# CAN_Shield_Board5.net
KiCad netlist of a schematic drawn in EAGLE
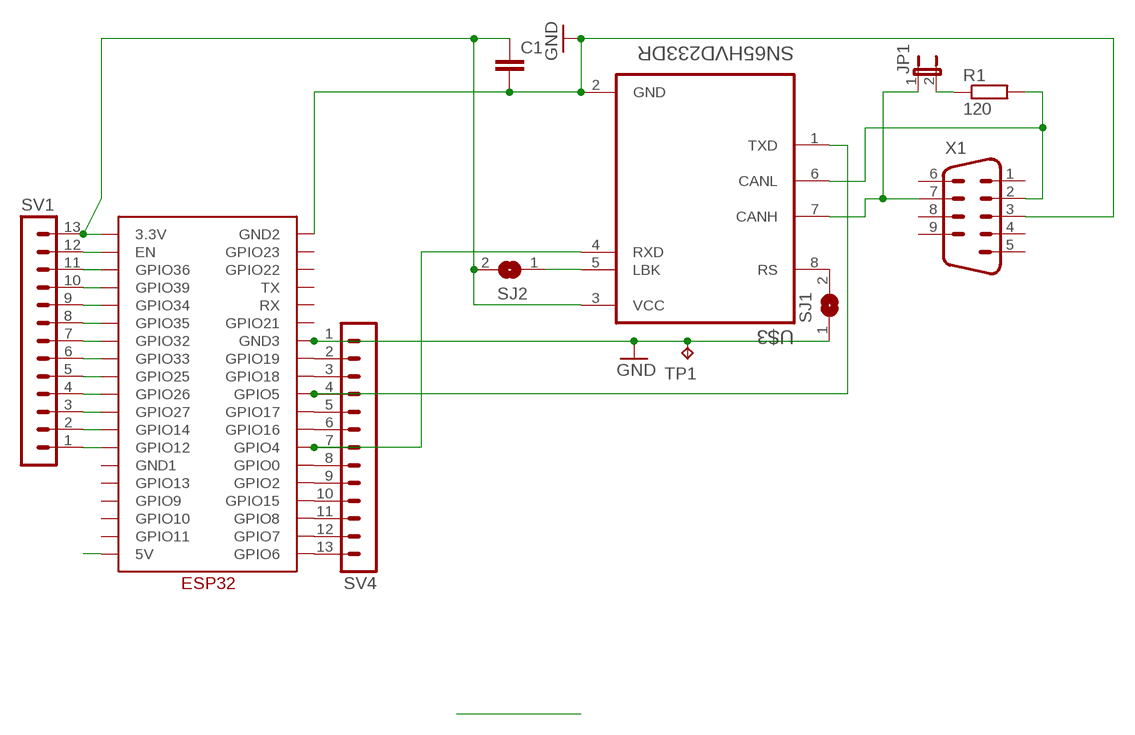
[diagram p0: schematic, sheet 1]

(export (version "E")
  (design (tool "Eeschema 10.0.6"))
  (components
    (comp (ref "C1")
      (value "C-EUC0805")
      (footprint "eagle-import:C0805")
      (libsource (lib "eagle-import") (part "C-EUC0805"))
    )
    (comp (ref "JP1")
      (value "JP1E")
      (footprint "eagle-import:JP1")
      (libsource (lib "eagle-import") (part "JP1E"))
    )
    (comp (ref "R1")
      (value "120")
      (footprint "eagle-import:R0805")
      (libsource (lib "eagle-import") (part "R-EU_R0805"))
    )
    (comp (ref "SJ1") (value "SJ") (footprint "eagle-import:SJ") (libsource (lib "eagle-import") (part "SJ")))
    (comp (ref "SJ2") (value "SJ") (footprint "eagle-import:SJ") (libsource (lib "eagle-import") (part "SJ")))
    (comp (ref "SV1")
      (value "MA13-1")
      (footprint "eagle-import:MA13-1")
      (libsource (lib "eagle-import") (part "MA13-1"))
    )
    (comp (ref "SV4")
      (value "MA13-1")
      (footprint "eagle-import:MA13-1")
      (libsource (lib "eagle-import") (part "MA13-1"))
    )
    (comp (ref "TP1")
      (value "TPPAD1-13Y")
      (footprint "eagle-import:P1-13Y")
      (libsource (lib "eagle-import") (part "TPPAD1-13Y"))
    )
    (comp (ref "U$1")
      (value "ESP32")
      (footprint "eagle-import:ESP32")
      (libsource (lib "eagle-import") (part "ESP32"))
    )
    (comp (ref "U$3")
      (value "SN65HVD233DR")
      (footprint "eagle-import:SOIC127P599X175-8N")
      (fields (field (name "MF") "Texas Instruments"))
      (libsource (lib "eagle-import") (part "SN65HVD233DR"))
    )
    (comp (ref "X1")
      (value "M09HP")
      (footprint "eagle-import:M09HP")
      (libsource (lib "eagle-import") (part "M09HP"))
    )
  )
  (nets
    (net (code "1") (name "GND") (class "Default")
      (node (ref "C1") (pin "2") (pinfunction "2_2") (pintype "passive"))
      (node (ref "SJ1") (pin "1") (pinfunction "1_1") (pintype "passive"))
      (node (ref "SV4") (pin "1") (pinfunction "1_1") (pintype "passive"))
      (node (ref "TP1") (pin "TP") (pinfunction "TP_TP") (pintype "input"))
      (node (ref "U$1") (pin "GND2") (pinfunction "GND2_GND2") (pintype "bidirectional"))
      (node (ref "U$1") (pin "GND3") (pinfunction "GND3_GND3") (pintype "bidirectional"))
      (node (ref "U$3") (pin "2") (pinfunction "GND_2") (pintype "power_in"))
      (node (ref "X1") (pin "3") (pinfunction "3_3") (pintype "passive"))
    )
    (net (code "2") (name "Net-(JP1-Pad2)") (class "Default")
      (node (ref "JP1") (pin "2") (pinfunction "2_2") (pintype "passive"))
      (node (ref "R1") (pin "1") (pinfunction "1_1") (pintype "passive"))
    )
    (net (code "3") (name "Net-(SV1-Pad1)") (class "Default")
      (node (ref "SV1") (pin "1") (pinfunction "1_1") (pintype "passive"))
      (node (ref "U$1") (pin "GPIO12") (pinfunction "GPIO12_GPIO12") (pintype "bidirectional"))
    )
    (net (code "4") (name "Net-(SV1-Pad2)") (class "Default")
      (node (ref "SV1") (pin "2") (pinfunction "2_2") (pintype "passive"))
      (node (ref "U$1") (pin "GPIO14") (pinfunction "GPIO14_GPIO14") (pintype "bidirectional"))
    )
    (net (code "5") (name "Net-(SV1-Pad3)") (class "Default")
      (node (ref "SV1") (pin "3") (pinfunction "3_3") (pintype "passive"))
      (node (ref "U$1") (pin "GPIO27") (pinfunction "GPIO27_GPIO27") (pintype "bidirectional"))
    )
    (net (code "6") (name "Net-(SV1-Pad4)") (class "Default")
      (node (ref "SV1") (pin "4") (pinfunction "4_4") (pintype "passive"))
      (node (ref "U$1") (pin "GPIO26") (pinfunction "GPIO26_GPIO26") (pintype "bidirectional"))
    )
    (net (code "7") (name "Net-(SV1-Pad5)") (class "Default")
      (node (ref "SV1") (pin "5") (pinfunction "5_5") (pintype "passive"))
      (node (ref "U$1") (pin "GPIO25") (pinfunction "GPIO25_GPIO25") (pintype "bidirectional"))
    )
    (net (code "8") (name "Net-(SV1-Pad6)") (class "Default")
      (node (ref "SV1") (pin "6") (pinfunction "6_6") (pintype "passive"))
      (node (ref "U$1") (pin "GPIO33") (pinfunction "GPIO33_GPIO33") (pintype "bidirectional"))
    )
    (net (code "9") (name "Net-(SV1-Pad7)") (class "Default")
      (node (ref "SV1") (pin "7") (pinfunction "7_7") (pintype "passive"))
      (node (ref "U$1") (pin "GPIO32") (pinfunction "GPIO32_GPIO32") (pintype "bidirectional"))
    )
    (net (code "10") (name "Net-(SV1-Pad8)") (class "Default")
      (node (ref "SV1") (pin "8") (pinfunction "8_8") (pintype "passive"))
      (node (ref "U$1") (pin "GPIO35") (pinfunction "GPIO35_GPIO35") (pintype "bidirectional"))
    )
    (net (code "11") (name "Net-(SV1-Pad9)") (class "Default")
      (node (ref "SV1") (pin "9") (pinfunction "9_9") (pintype "passive"))
      (node (ref "U$1") (pin "GPIO34") (pinfunction "GPIO34_GPIO34") (pintype "bidirectional"))
    )
    (net (code "12") (name "Net-(SV1-Pad10)") (class "Default")
      (node (ref "SV1") (pin "10") (pinfunction "10_10") (pintype "passive"))
      (node (ref "U$1") (pin "GPIO39") (pinfunction "GPIO39_GPIO39") (pintype "bidirectional"))
    )
    (net (code "13") (name "Net-(SV1-Pad11)") (class "Default")
      (node (ref "SV1") (pin "11") (pinfunction "11_11") (pintype "passive"))
      (node (ref "U$1") (pin "GPIO36") (pinfunction "GPIO36_GPIO36") (pintype "bidirectional"))
    )
    (net (code "14") (name "Net-(SV1-Pad12)") (class "Default")
      (node (ref "SV1") (pin "12") (pinfunction "12_12") (pintype "passive"))
      (node (ref "U$1") (pin "EN") (pinfunction "EN_EN") (pintype "bidirectional"))
    )
    (net (code "15") (name "Net-(SV4-Pad2)") (class "Default")
      (node (ref "SV4") (pin "2") (pinfunction "2_2") (pintype "passive"))
      (node (ref "U$1") (pin "GPIO19") (pinfunction "GPIO19_GPIO19") (pintype "bidirectional"))
    )
    (net (code "16") (name "Net-(SV4-Pad3)") (class "Default")
      (node (ref "SV4") (pin "3") (pinfunction "3_3") (pintype "passive"))
      (node (ref "U$1") (pin "GPIO18") (pinfunction "GPIO18_GPIO18") (pintype "bidirectional"))
    )
    (net (code "17") (name "Net-(SV4-Pad5)") (class "Default")
      (node (ref "SV4") (pin "5") (pinfunction "5_5") (pintype "passive"))
      (node (ref "U$1") (pin "GPIO17") (pinfunction "GPIO17_GPIO17") (pintype "bidirectional"))
    )
    (net (code "18") (name "Net-(SV4-Pad6)") (class "Default")
      (node (ref "SV4") (pin "6") (pinfunction "6_6") (pintype "passive"))
      (node (ref "U$1") (pin "GPIO16") (pinfunction "GPIO16_GPIO16") (pintype "bidirectional"))
    )
    (net (code "19") (name "Net-(SV4-Pad8)") (class "Default")
      (node (ref "SV4") (pin "8") (pinfunction "8_8") (pintype "passive"))
      (node (ref "U$1") (pin "GPIO0") (pinfunction "GPIO0_GPIO0") (pintype "bidirectional"))
    )
    (net (code "20") (name "Net-(SV4-Pad9)") (class "Default")
      (node (ref "SV4") (pin "9") (pinfunction "9_9") (pintype "passive"))
      (node (ref "U$1") (pin "GPIO2") (pinfunction "GPIO2_GPIO2") (pintype "bidirectional"))
    )
    (net (code "21") (name "Net-(SV4-Pad10)") (class "Default")
      (node (ref "SV4") (pin "10") (pinfunction "10_10") (pintype "passive"))
      (node (ref "U$1") (pin "GPIO15") (pinfunction "GPIO15_GPIO15") (pintype "bidirectional"))
    )
    (net (code "22") (name "Net-(SV4-Pad11)") (class "Default")
      (node (ref "SV4") (pin "11") (pinfunction "11_11") (pintype "passive"))
      (node (ref "U$1") (pin "GPIO8") (pinfunction "GPIO8_GPIO8") (pintype "bidirectional"))
    )
    (net (code "23") (name "Net-(SV4-Pad12)") (class "Default")
      (node (ref "SV4") (pin "12") (pinfunction "12_12") (pintype "passive"))
      (node (ref "U$1") (pin "GPIO7") (pinfunction "GPIO7_GPIO7") (pintype "bidirectional"))
    )
    (net (code "24") (name "Net-(SV4-Pad13)") (class "Default")
      (node (ref "SV4") (pin "13") (pinfunction "13_13") (pintype "passive"))
      (node (ref "U$1") (pin "GPIO6") (pinfunction "GPIO6_GPIO6") (pintype "bidirectional"))
    )
    (net (code "25") (name "Net-(U$3-CANH)") (class "Default")
      (node (ref "JP1") (pin "1") (pinfunction "1_1") (pintype "passive"))
      (node (ref "U$3") (pin "7") (pinfunction "CANH_7") (pintype "bidirectional"))
      (node (ref "X1") (pin "7") (pinfunction "7_7") (pintype "passive"))
    )
    (net (code "26") (name "Net-(U$3-CANL)") (class "Default")
      (node (ref "R1") (pin "2") (pinfunction "2_2") (pintype "passive"))
      (node (ref "U$3") (pin "6") (pinfunction "CANL_6") (pintype "bidirectional"))
      (node (ref "X1") (pin "2") (pinfunction "2_2") (pintype "passive"))
    )
    (net (code "27") (name "Net-(U$3-LBK)") (class "Default")
      (node (ref "SJ2") (pin "1") (pinfunction "1_1") (pintype "passive"))
      (node (ref "U$3") (pin "5") (pinfunction "LBK_5") (pintype "output"))
    )
    (net (code "28") (name "Net-(U$3-RS)") (class "Default")
      (node (ref "SJ1") (pin "2") (pinfunction "2_2") (pintype "passive"))
      (node (ref "U$3") (pin "8") (pinfunction "RS_8") (pintype "input"))
    )
    (net (code "29") (name "Net-(U$3-RXD)") (class "Default")
      (node (ref "SV4") (pin "7") (pinfunction "7_7") (pintype "passive"))
      (node (ref "U$1") (pin "GPIO4") (pinfunction "GPIO4_GPIO4") (pintype "bidirectional"))
      (node (ref "U$3") (pin "4") (pinfunction "RXD_4") (pintype "output"))
    )
    (net (code "30") (name "Net-(U$3-TXD)") (class "Default")
      (node (ref "SV4") (pin "4") (pinfunction "4_4") (pintype "passive"))
      (node (ref "U$1") (pin "GPIO5") (pinfunction "GPIO5_GPIO5") (pintype "bidirectional"))
      (node (ref "U$3") (pin "1") (pinfunction "TXD_1") (pintype "bidirectional"))
    )
    (net (code "31") (name "Net-(U$3-VCC)") (class "Default")
      (node (ref "C1") (pin "1") (pinfunction "1_1") (pintype "passive"))
      (node (ref "SJ2") (pin "2") (pinfunction "2_2") (pintype "passive"))
      (node (ref "SV1") (pin "13") (pinfunction "13_13") (pintype "passive"))
      (node (ref "U$1") (pin "3.3V") (pinfunction "3.3V_3.3V") (pintype "bidirectional"))
      (node (ref "U$3") (pin "3") (pinfunction "VCC_3") (pintype "power_in"))
    )
    (net (code "32") (name "unconnected-(U$1-Pad5V)") (class "Default")
      (node (ref "U$1") (pin "5V") (pinfunction "5V_5V") (pintype "bidirectional"))
    )
    (net (code "33") (name "unconnected-(U$1-PadGND1)") (class "Default")
      (node (ref "U$1") (pin "GND1") (pinfunction "GND1_GND1") (pintype "bidirectional"))
    )
    (net (code "34") (name "unconnected-(U$1-PadGPIO9)") (class "Default")
      (node (ref "U$1") (pin "GPIO9") (pinfunction "GPIO9_GPIO9") (pintype "bidirectional"))
    )
    (net (code "35") (name "unconnected-(U$1-PadGPIO10)") (class "Default")
      (node (ref "U$1") (pin "GPIO10") (pinfunction "GPIO10_GPIO10") (pintype "bidirectional"))
    )
    (net (code "36") (name "unconnected-(U$1-PadGPIO11)") (class "Default")
      (node (ref "U$1") (pin "GPIO11") (pinfunction "GPIO11_GPIO11") (pintype "bidirectional"))
    )
    (net (code "37") (name "unconnected-(U$1-PadGPIO13)") (class "Default")
      (node (ref "U$1") (pin "GPIO13") (pinfunction "GPIO13_GPIO13") (pintype "bidirectional"))
    )
    (net (code "38") (name "unconnected-(U$1-PadGPIO21)") (class "Default")
      (node (ref "U$1") (pin "GPIO21") (pinfunction "GPIO21_GPIO21") (pintype "bidirectional"))
    )
    (net (code "39") (name "unconnected-(U$1-PadGPIO22)") (class "Default")
      (node (ref "U$1") (pin "GPIO22") (pinfunction "GPIO22_GPIO22") (pintype "bidirectional"))
    )
    (net (code "40") (name "unconnected-(U$1-PadGPIO23)") (class "Default")
      (node (ref "U$1") (pin "GPIO23") (pinfunction "GPIO23_GPIO23") (pintype "bidirectional"))
    )
    (net (code "41") (name "unconnected-(U$1-PadRX)") (class "Default")
      (node (ref "U$1") (pin "RX") (pinfunction "RX_RX") (pintype "bidirectional"))
    )
    (net (code "42") (name "unconnected-(U$1-PadTX)") (class "Default")
      (node (ref "U$1") (pin "TX") (pinfunction "TX_TX") (pintype "bidirectional"))
    )
    (net (code "43") (name "unconnected-(X1-Pad1)") (class "Default")
      (node (ref "X1") (pin "1") (pinfunction "1_1") (pintype "passive"))
    )
    (net (code "44") (name "unconnected-(X1-Pad4)") (class "Default")
      (node (ref "X1") (pin "4") (pinfunction "4_4") (pintype "passive"))
    )
    (net (code "45") (name "unconnected-(X1-Pad5)") (class "Default")
      (node (ref "X1") (pin "5") (pinfunction "5_5") (pintype "passive"))
    )
    (net (code "46") (name "unconnected-(X1-Pad6)") (class "Default")
      (node (ref "X1") (pin "6") (pinfunction "6_6") (pintype "passive"))
    )
    (net (code "47") (name "unconnected-(X1-Pad8)") (class "Default")
      (node (ref "X1") (pin "8") (pinfunction "8_8") (pintype "passive"))
    )
    (net (code "48") (name "unconnected-(X1-Pad9)") (class "Default")
      (node (ref "X1") (pin "9") (pinfunction "9_9") (pintype "passive"))
    )
  )
)
